# ActuatorMKII_Microcontroller.net
KiCad netlist of a schematic drawn in Altium Designer
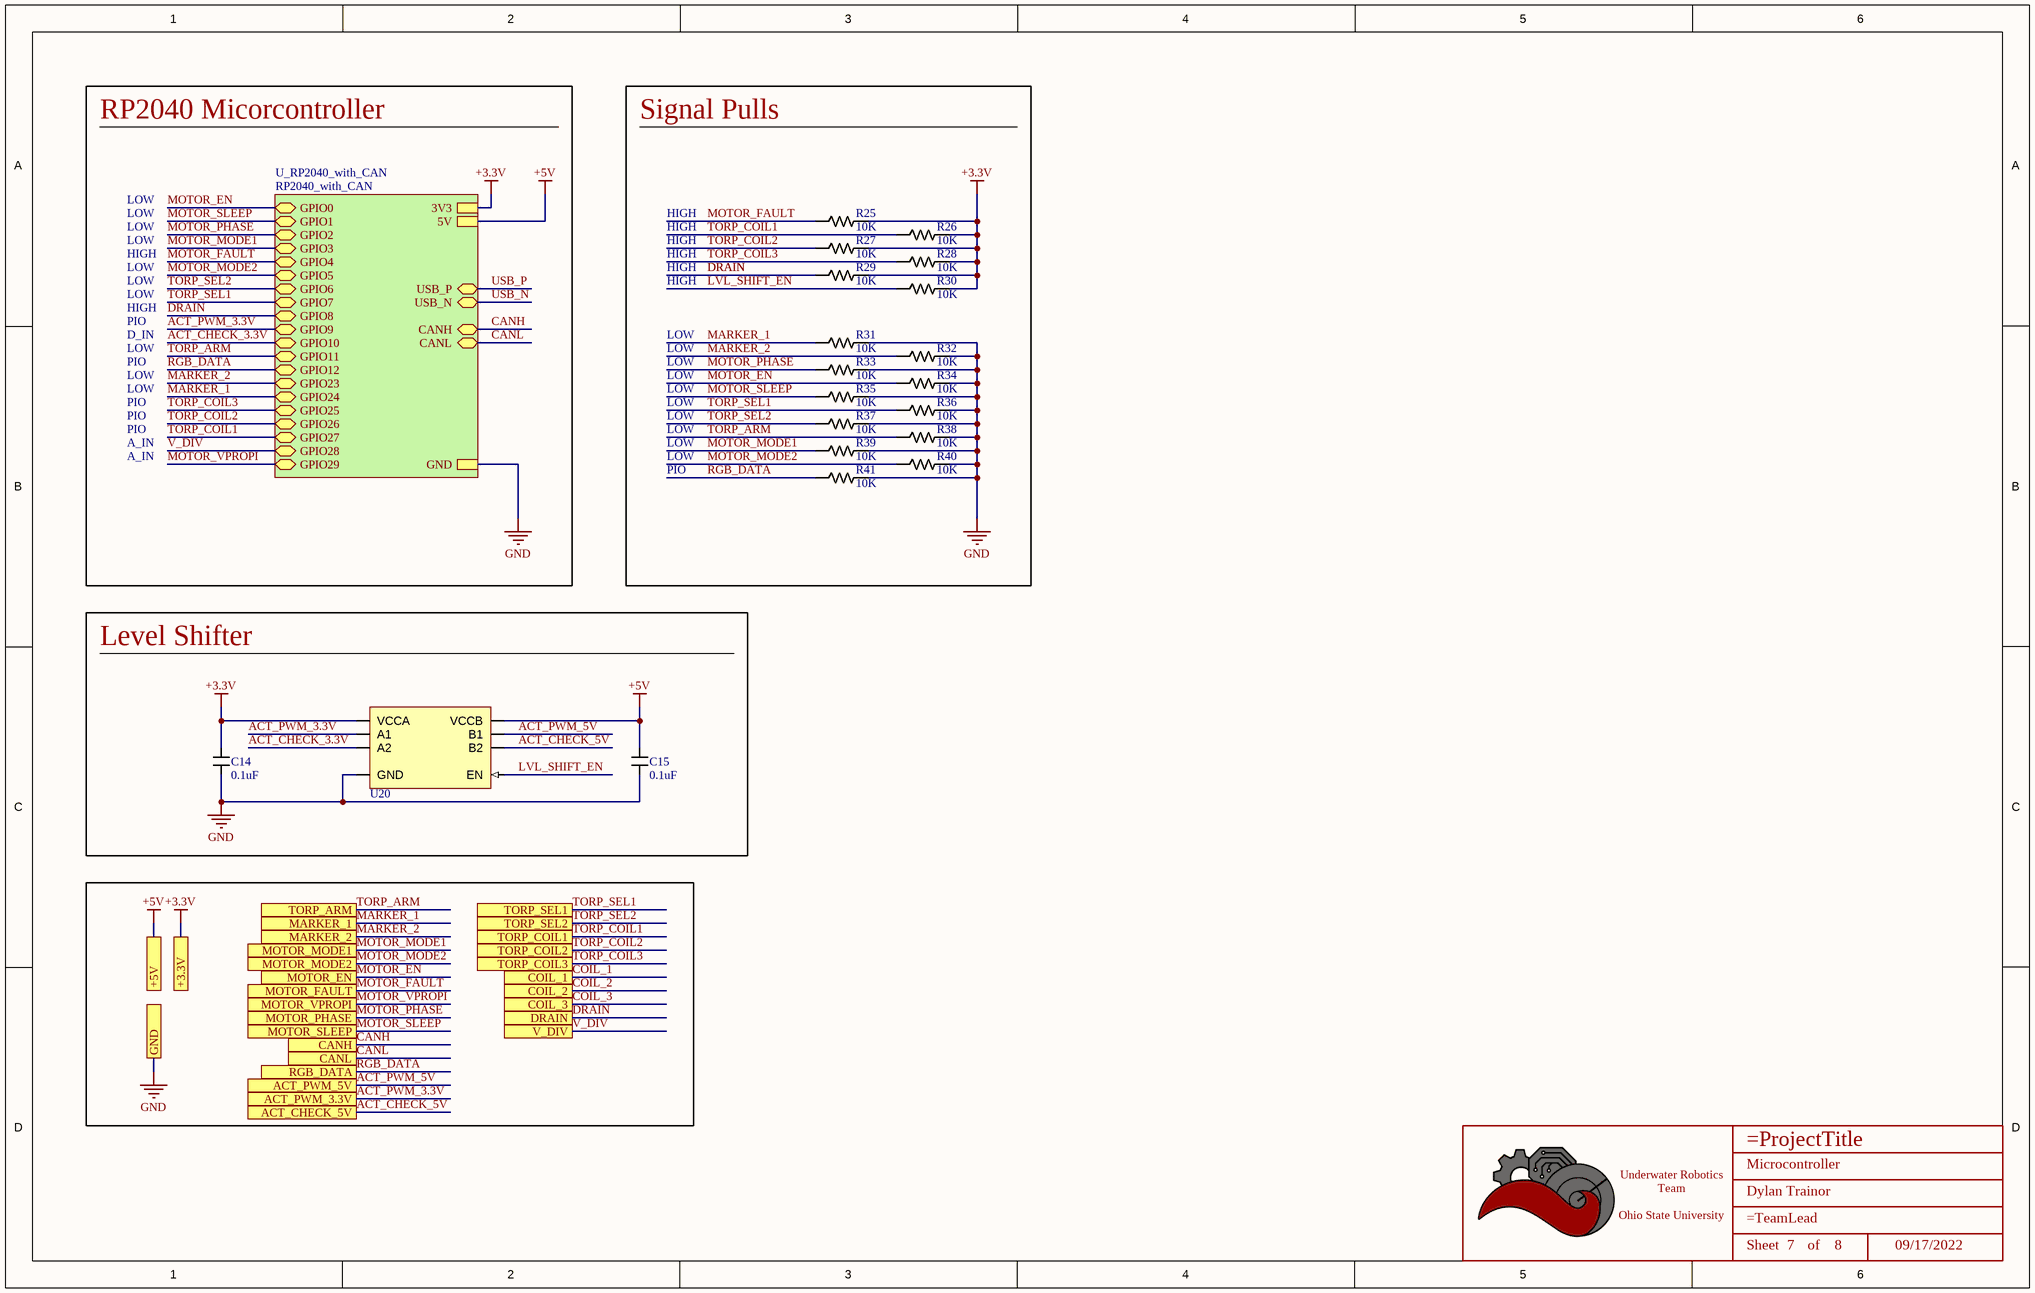
[diagram p0: ActuatorMKII_Microcontroller.SchDoc]

(export (version "E")
  (design (tool "Eeschema 10.0.6"))
  (components
    (comp (ref "*")
      (value "Title_Block")
      (footprint "LOGO")
      (description "UWRT Schematic Title Block Template\r\n\r\nCreated June 2021, Dylan Trainor")
      (libsource (lib "UWRT") (part "Title_Block"))
    )
    (comp (ref "C14")
      (value "0.1uF")
      (footprint "CAPACITOR_0603")
      (description "Cap 100nF 6.3V +/-10%\r\nCeramic 0603")
      (fields
        (field (name "TOLERANCE") "+/- 10%")
        (field (name "VOLTAGE") "6.3V")
        (field (name "MADE BY") "Flip B")
      )
      (libsource (lib "Capacitors") (part "CAPACITOR_0.1uF_0603"))
    )
    (comp (ref "C15")
      (value "0.1uF")
      (footprint "CAPACITOR_0603")
      (description "Cap 100nF 6.3V +/-10%\r\nCeramic 0603")
      (fields
        (field (name "TOLERANCE") "+/- 10%")
        (field (name "VOLTAGE") "6.3V")
        (field (name "MADE BY") "Flip B")
      )
      (libsource (lib "Capacitors") (part "CAPACITOR_0.1uF_0603"))
    )
    (comp (ref "R25")
      (value "10k Ohm 5% 1/10W")
      (footprint "RESISTOR_0603")
      (description "RES 10k OHM 5% 1/10W 0603")
      (fields
        (field (name "TOLERANCE") "+/- 5%")
        (field (name "VALUE  (OHMS)") "10K")
        (field (name "MADE BY") "Robert Pafford")
      )
      (libsource (lib "Resistors") (part "RESISTOR_10K_0603"))
    )
    (comp (ref "R26")
      (value "10k Ohm 5% 1/10W")
      (footprint "RESISTOR_0603")
      (description "RES 10k OHM 5% 1/10W 0603")
      (fields
        (field (name "TOLERANCE") "+/- 5%")
        (field (name "VALUE  (OHMS)") "10K")
        (field (name "MADE BY") "Robert Pafford")
      )
      (libsource (lib "Resistors") (part "RESISTOR_10K_0603"))
    )
    (comp (ref "R27")
      (value "10k Ohm 5% 1/10W")
      (footprint "RESISTOR_0603")
      (description "RES 10k OHM 5% 1/10W 0603")
      (fields
        (field (name "TOLERANCE") "+/- 5%")
        (field (name "VALUE  (OHMS)") "10K")
        (field (name "MADE BY") "Robert Pafford")
      )
      (libsource (lib "Resistors") (part "RESISTOR_10K_0603"))
    )
    (comp (ref "R28")
      (value "10k Ohm 5% 1/10W")
      (footprint "RESISTOR_0603")
      (description "RES 10k OHM 5% 1/10W 0603")
      (fields
        (field (name "TOLERANCE") "+/- 5%")
        (field (name "VALUE  (OHMS)") "10K")
        (field (name "MADE BY") "Robert Pafford")
      )
      (libsource (lib "Resistors") (part "RESISTOR_10K_0603"))
    )
    (comp (ref "R29")
      (value "10k Ohm 5% 1/10W")
      (footprint "RESISTOR_0603")
      (description "RES 10k OHM 5% 1/10W 0603")
      (fields
        (field (name "TOLERANCE") "+/- 5%")
        (field (name "VALUE  (OHMS)") "10K")
        (field (name "MADE BY") "Robert Pafford")
      )
      (libsource (lib "Resistors") (part "RESISTOR_10K_0603"))
    )
    (comp (ref "R30")
      (value "10k Ohm 5% 1/10W")
      (footprint "RESISTOR_0603")
      (description "RES 10k OHM 5% 1/10W 0603")
      (fields
        (field (name "TOLERANCE") "+/- 5%")
        (field (name "VALUE  (OHMS)") "10K")
        (field (name "MADE BY") "Robert Pafford")
      )
      (libsource (lib "Resistors") (part "RESISTOR_10K_0603"))
    )
    (comp (ref "R31")
      (value "10k Ohm 5% 1/10W")
      (footprint "RESISTOR_0603")
      (description "RES 10k OHM 5% 1/10W 0603")
      (fields
        (field (name "TOLERANCE") "+/- 5%")
        (field (name "VALUE  (OHMS)") "10K")
        (field (name "MADE BY") "Robert Pafford")
      )
      (libsource (lib "Resistors") (part "RESISTOR_10K_0603"))
    )
    (comp (ref "R32")
      (value "10k Ohm 5% 1/10W")
      (footprint "RESISTOR_0603")
      (description "RES 10k OHM 5% 1/10W 0603")
      (fields
        (field (name "TOLERANCE") "+/- 5%")
        (field (name "VALUE  (OHMS)") "10K")
        (field (name "MADE BY") "Robert Pafford")
      )
      (libsource (lib "Resistors") (part "RESISTOR_10K_0603"))
    )
    (comp (ref "R33")
      (value "10k Ohm 5% 1/10W")
      (footprint "RESISTOR_0603")
      (description "RES 10k OHM 5% 1/10W 0603")
      (fields
        (field (name "TOLERANCE") "+/- 5%")
        (field (name "VALUE  (OHMS)") "10K")
        (field (name "MADE BY") "Robert Pafford")
      )
      (libsource (lib "Resistors") (part "RESISTOR_10K_0603"))
    )
    (comp (ref "R34")
      (value "10k Ohm 5% 1/10W")
      (footprint "RESISTOR_0603")
      (description "RES 10k OHM 5% 1/10W 0603")
      (fields
        (field (name "TOLERANCE") "+/- 5%")
        (field (name "VALUE  (OHMS)") "10K")
        (field (name "MADE BY") "Robert Pafford")
      )
      (libsource (lib "Resistors") (part "RESISTOR_10K_0603"))
    )
    (comp (ref "R35")
      (value "10k Ohm 5% 1/10W")
      (footprint "RESISTOR_0603")
      (description "RES 10k OHM 5% 1/10W 0603")
      (fields
        (field (name "TOLERANCE") "+/- 5%")
        (field (name "VALUE  (OHMS)") "10K")
        (field (name "MADE BY") "Robert Pafford")
      )
      (libsource (lib "Resistors") (part "RESISTOR_10K_0603"))
    )
    (comp (ref "R36")
      (value "10k Ohm 5% 1/10W")
      (footprint "RESISTOR_0603")
      (description "RES 10k OHM 5% 1/10W 0603")
      (fields
        (field (name "TOLERANCE") "+/- 5%")
        (field (name "VALUE  (OHMS)") "10K")
        (field (name "MADE BY") "Robert Pafford")
      )
      (libsource (lib "Resistors") (part "RESISTOR_10K_0603"))
    )
    (comp (ref "R37")
      (value "10k Ohm 5% 1/10W")
      (footprint "RESISTOR_0603")
      (description "RES 10k OHM 5% 1/10W 0603")
      (fields
        (field (name "TOLERANCE") "+/- 5%")
        (field (name "VALUE  (OHMS)") "10K")
        (field (name "MADE BY") "Robert Pafford")
      )
      (libsource (lib "Resistors") (part "RESISTOR_10K_0603"))
    )
    (comp (ref "R38")
      (value "10k Ohm 5% 1/10W")
      (footprint "RESISTOR_0603")
      (description "RES 10k OHM 5% 1/10W 0603")
      (fields
        (field (name "TOLERANCE") "+/- 5%")
        (field (name "VALUE  (OHMS)") "10K")
        (field (name "MADE BY") "Robert Pafford")
      )
      (libsource (lib "Resistors") (part "RESISTOR_10K_0603"))
    )
    (comp (ref "R39")
      (value "10k Ohm 5% 1/10W")
      (footprint "RESISTOR_0603")
      (description "RES 10k OHM 5% 1/10W 0603")
      (fields
        (field (name "TOLERANCE") "+/- 5%")
        (field (name "VALUE  (OHMS)") "10K")
        (field (name "MADE BY") "Robert Pafford")
      )
      (libsource (lib "Resistors") (part "RESISTOR_10K_0603"))
    )
    (comp (ref "R40")
      (value "10k Ohm 5% 1/10W")
      (footprint "RESISTOR_0603")
      (description "RES 10k OHM 5% 1/10W 0603")
      (fields
        (field (name "TOLERANCE") "+/- 5%")
        (field (name "VALUE  (OHMS)") "10K")
        (field (name "MADE BY") "Robert Pafford")
      )
      (libsource (lib "Resistors") (part "RESISTOR_10K_0603"))
    )
    (comp (ref "R41")
      (value "10k Ohm 5% 1/10W")
      (footprint "RESISTOR_0603")
      (description "RES 10k OHM 5% 1/10W 0603")
      (fields
        (field (name "TOLERANCE") "+/- 5%")
        (field (name "VALUE  (OHMS)") "10K")
        (field (name "MADE BY") "Robert Pafford")
      )
      (libsource (lib "Resistors") (part "RESISTOR_10K_0603"))
    )
    (comp (ref "U20")
      (value "IC TRANSLTR BIDIRECTIONAL 8MSOP")
      (footprint "MSOP-8_PI4ULS5V202UEX")
      (description "Voltage Level Translator Bidirectional 1 Circuit 2 Channel 20Mbps 8-MSOP")
      (fields (field (name "MADE BY") "Robert Pafford"))
      (libsource (lib "Integrated Circuits") (part "PI4ULS5V202UEX"))
    )
  )
  (nets
    (net (code "1") (name "+3.3V") (class "Default")
      (node (ref "C14") (pin "1") (pinfunction "1_1") (pintype "passive"))
      (node (ref "R25") (pin "1") (pinfunction "1_1") (pintype "passive"))
      (node (ref "R26") (pin "1") (pinfunction "1_1") (pintype "passive"))
      (node (ref "R27") (pin "1") (pinfunction "1_1") (pintype "passive"))
      (node (ref "R28") (pin "1") (pinfunction "1_1") (pintype "passive"))
      (node (ref "R29") (pin "1") (pinfunction "1_1") (pintype "passive"))
      (node (ref "R30") (pin "1") (pinfunction "1_1") (pintype "passive"))
      (node (ref "U20") (pin "1") (pinfunction "VCCA_1") (pintype "power_in"))
    )
    (net (code "2") (name "+5V") (class "Default")
      (node (ref "C15") (pin "1") (pinfunction "1_1") (pintype "passive"))
      (node (ref "U20") (pin "8") (pinfunction "VCCB_8") (pintype "power_in"))
    )
    (net (code "3") (name "/ACT_CHECK_3.3V") (class "Default")
      (node (ref "U20") (pin "3") (pinfunction "A2_3") (pintype "bidirectional"))
    )
    (net (code "4") (name "/ACT_CHECK_5V") (class "Default")
      (node (ref "U20") (pin "6") (pinfunction "B2_6") (pintype "bidirectional"))
    )
    (net (code "5") (name "/ACT_PWM_3.3V") (class "Default")
      (node (ref "U20") (pin "2") (pinfunction "A1_2") (pintype "bidirectional"))
    )
    (net (code "6") (name "/ACT_PWM_5V") (class "Default")
      (node (ref "U20") (pin "7") (pinfunction "B1_7") (pintype "bidirectional"))
    )
    (net (code "12") (name "/DRAIN") (class "Default")
      (node (ref "R29") (pin "2") (pinfunction "2_2") (pintype "passive"))
    )
    (net (code "13") (name "/LVL_SHIFT_EN") (class "Default")
      (node (ref "R30") (pin "2") (pinfunction "2_2") (pintype "passive"))
      (node (ref "U20") (pin "5") (pinfunction "EN_5") (pintype "input"))
    )
    (net (code "14") (name "/MARKER_1") (class "Default")
      (node (ref "R31") (pin "2") (pinfunction "2_2") (pintype "passive"))
    )
    (net (code "15") (name "/MARKER_2") (class "Default")
      (node (ref "R32") (pin "2") (pinfunction "2_2") (pintype "passive"))
    )
    (net (code "16") (name "/MOTOR_EN") (class "Default")
      (node (ref "R34") (pin "2") (pinfunction "2_2") (pintype "passive"))
    )
    (net (code "17") (name "/MOTOR_FAULT") (class "Default")
      (node (ref "R25") (pin "2") (pinfunction "2_2") (pintype "passive"))
    )
    (net (code "18") (name "/MOTOR_MODE1") (class "Default")
      (node (ref "R39") (pin "2") (pinfunction "2_2") (pintype "passive"))
    )
    (net (code "19") (name "/MOTOR_MODE2") (class "Default")
      (node (ref "R40") (pin "2") (pinfunction "2_2") (pintype "passive"))
    )
    (net (code "20") (name "/MOTOR_PHASE") (class "Default")
      (node (ref "R33") (pin "2") (pinfunction "2_2") (pintype "passive"))
    )
    (net (code "21") (name "/MOTOR_SLEEP") (class "Default")
      (node (ref "R35") (pin "2") (pinfunction "2_2") (pintype "passive"))
    )
    (net (code "23") (name "/RGB_DATA") (class "Default")
      (node (ref "R41") (pin "2") (pinfunction "2_2") (pintype "passive"))
    )
    (net (code "24") (name "/TORP_ARM") (class "Default")
      (node (ref "R38") (pin "2") (pinfunction "2_2") (pintype "passive"))
    )
    (net (code "25") (name "/TORP_COIL1") (class "Default")
      (node (ref "R26") (pin "2") (pinfunction "2_2") (pintype "passive"))
    )
    (net (code "26") (name "/TORP_COIL2") (class "Default")
      (node (ref "R27") (pin "2") (pinfunction "2_2") (pintype "passive"))
    )
    (net (code "27") (name "/TORP_COIL3") (class "Default")
      (node (ref "R28") (pin "2") (pinfunction "2_2") (pintype "passive"))
    )
    (net (code "28") (name "/TORP_SEL1") (class "Default")
      (node (ref "R36") (pin "2") (pinfunction "2_2") (pintype "passive"))
    )
    (net (code "29") (name "/TORP_SEL2") (class "Default")
      (node (ref "R37") (pin "2") (pinfunction "2_2") (pintype "passive"))
    )
    (net (code "33") (name "GND") (class "Default")
      (node (ref "C14") (pin "2") (pinfunction "2_2") (pintype "passive"))
      (node (ref "C15") (pin "2") (pinfunction "2_2") (pintype "passive"))
      (node (ref "R31") (pin "1") (pinfunction "1_1") (pintype "passive"))
      (node (ref "R32") (pin "1") (pinfunction "1_1") (pintype "passive"))
      (node (ref "R33") (pin "1") (pinfunction "1_1") (pintype "passive"))
      (node (ref "R34") (pin "1") (pinfunction "1_1") (pintype "passive"))
      (node (ref "R35") (pin "1") (pinfunction "1_1") (pintype "passive"))
      (node (ref "R36") (pin "1") (pinfunction "1_1") (pintype "passive"))
      (node (ref "R37") (pin "1") (pinfunction "1_1") (pintype "passive"))
      (node (ref "R38") (pin "1") (pinfunction "1_1") (pintype "passive"))
      (node (ref "R39") (pin "1") (pinfunction "1_1") (pintype "passive"))
      (node (ref "R40") (pin "1") (pinfunction "1_1") (pintype "passive"))
      (node (ref "R41") (pin "1") (pinfunction "1_1") (pintype "passive"))
      (node (ref "U20") (pin "4") (pinfunction "GND_4") (pintype "power_in"))
    )
  )
)
